# MioMicro.net
KiCad netlist of a schematic drawn in Altium Designer
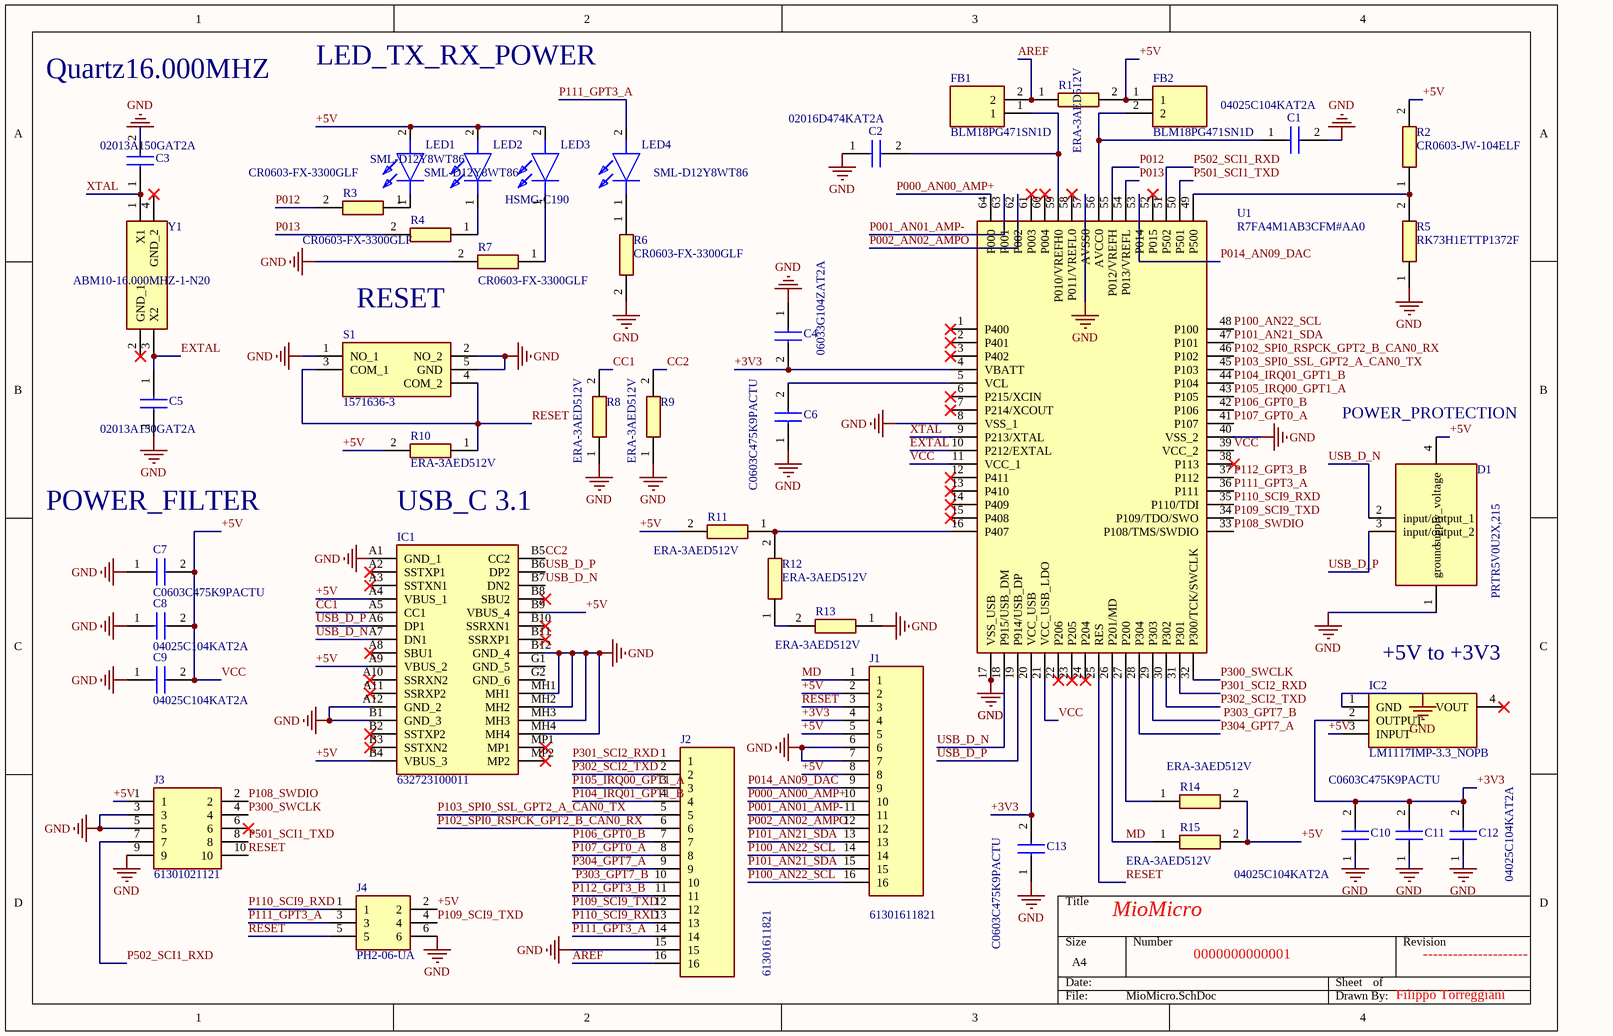
[diagram p0: MioMicro.SchDoc]

(export (version "E")
  (design (tool "Eeschema 10.0.6"))
  (components
    (comp (ref "C1")
      (value "04025C104KAT2A")
      (footprint "MioMicro:CAPC1005X56N")
      (description "Capacitor")
      (fields (field (name "MOUSER PART NUMBER") "581-04025C104KAT2A"))
      (libsource (lib "*") (part "04025C104KAT2A"))
    )
    (comp (ref "C2")
      (value "02016D474KAT2A")
      (footprint "MioMicro:CAPC0603X33N")
      (description "Capacitor")
      (fields (field (name "MOUSER PART NUMBER") "581-02016D474KAT2A"))
      (libsource (lib "*") (part "02016D474KAT2A"))
    )
    (comp (ref "C3")
      (value "02013A150GAT2A")
      (footprint "MioMicro:CAPC0603X33N")
      (description "Capacitor")
      (fields (field (name "MOUSER PART NUMBER") "581-02013A150GAT2A"))
      (libsource (lib "*") (part "02013A150GAT2A"))
    )
    (comp (ref "C4")
      (value "06033G104ZAT2A")
      (footprint "MioMicro:CAPC1608X90N")
      (description "Capacitor")
      (fields (field (name "MOUSER PART NUMBER") "581-06033G104Z"))
      (libsource (lib "*") (part "06033G104ZAT2A"))
    )
    (comp (ref "C5")
      (value "02013A150GAT2A")
      (footprint "MioMicro:CAPC0603X33N")
      (description "Capacitor")
      (fields (field (name "MOUSER PART NUMBER") "581-02013A150GAT2A"))
      (libsource (lib "*") (part "02013A150GAT2A"))
    )
    (comp (ref "C6")
      (value "C0603C475K9PACTU")
      (footprint "MioMicro:C0603")
      (description "Capacitor")
      (fields (field (name "MOUSER PART NUMBER") "80-C0603C475K9P"))
      (libsource (lib "*") (part "C0603C475K9PACTU"))
    )
    (comp (ref "C7")
      (value "C0603C475K9PACTU")
      (footprint "MioMicro:C0603")
      (description "Capacitor")
      (fields (field (name "MOUSER PART NUMBER") "80-C0603C475K9P"))
      (libsource (lib "*") (part "C0603C475K9PACTU"))
    )
    (comp (ref "C8")
      (value "04025C104KAT2A")
      (footprint "MioMicro:CAPC1005X56N")
      (description "Capacitor")
      (fields (field (name "MOUSER PART NUMBER") "581-04025C104KAT2A"))
      (libsource (lib "*") (part "04025C104KAT2A"))
    )
    (comp (ref "C9")
      (value "04025C104KAT2A")
      (footprint "MioMicro:CAPC1005X56N")
      (description "Capacitor")
      (fields (field (name "MOUSER PART NUMBER") "581-04025C104KAT2A"))
      (libsource (lib "*") (part "04025C104KAT2A"))
    )
    (comp (ref "C10")
      (value "C0603C475K9PACTU")
      (footprint "MioMicro:C0603")
      (description "Capacitor")
      (fields (field (name "MOUSER PART NUMBER") "80-C0603C475K9P"))
      (libsource (lib "*") (part "C0603C475K9PACTU"))
    )
    (comp (ref "C11")
      (value "04025C104KAT2A")
      (footprint "MioMicro:CAPC1005X56N")
      (description "Capacitor")
      (fields (field (name "MOUSER PART NUMBER") "581-04025C104KAT2A"))
      (libsource (lib "*") (part "04025C104KAT2A"))
    )
    (comp (ref "C12")
      (value "04025C104KAT2A")
      (footprint "MioMicro:CAPC1005X56N")
      (description "Capacitor")
      (fields (field (name "MOUSER PART NUMBER") "581-04025C104KAT2A"))
      (libsource (lib "*") (part "04025C104KAT2A"))
    )
    (comp (ref "C13")
      (value "C0603C475K9PACTU")
      (footprint "MioMicro:C0603")
      (description "Capacitor")
      (fields (field (name "MOUSER PART NUMBER") "80-C0603C475K9P"))
      (libsource (lib "*") (part "C0603C475K9PACTU"))
    )
    (comp (ref "D1")
      (value "PRTR5V0U2X,215")
      (footprint "MioMicro:PRTR5V0U2X")
      (description "Diode")
      (fields (field (name "MOUSER PART NUMBER") "771-PRTR5V0U2X-T/R"))
      (libsource (lib "*") (part "PRTR5V0U2X,215"))
    )
    (comp (ref "FB1")
      (value "BLM18PG471SN1D")
      (footprint "MioMicro:BLM18SP221SN1B")
      (description "Ferrite Bead")
      (fields (field (name "MOUSER PART NUMBER") "81-BLM18PG471SN1D"))
      (libsource (lib "") (part "BLM18PG471SN1D_1"))
    )
    (comp (ref "FB2")
      (value "BLM18PG471SN1D")
      (footprint "MioMicro:BLM18SP221SN1B")
      (description "Ferrite Bead")
      (fields (field (name "MOUSER PART NUMBER") "81-BLM18PG471SN1D"))
      (libsource (lib "*") (part "BLM18PG471SN1D"))
    )
    (comp (ref "IC1")
      (value "632723100011")
      (footprint "MioMicro:632723100011")
      (description "Integrated Circuit")
      (fields (field (name "MOUSER PART NUMBER") "710-632723100011"))
      (libsource (lib "*") (part "632723100011"))
    )
    (comp (ref "IC2")
      (value "LM1117IMP-3.3_NOPB")
      (footprint "MioMicro:SOT230P700X180-4N")
      (description "Integrated Circuit")
      (fields
        (field (name "MANUFACTURER_PART_NUMBER") "LM1117IMP-3.3/NOPB")
        (field (name "MOUSER PART NUMBER") "926-LM1117IMP3.3NOPB")
      )
      (libsource (lib "*") (part "LM1117IMP-3.3_NOPB"))
    )
    (comp (ref "J1")
      (value "61301611821")
      (footprint "MioMicro:RHDR16W82P0X254_1X16_4114X250X865P")
      (description "Connector")
      (fields (field (name "MOUSER PART NUMBER") "710-61301611821"))
      (libsource (lib "*") (part "61301611821"))
    )
    (comp (ref "J2")
      (value "61301611821")
      (footprint "MioMicro:RHDR16W82P0X254_1X16_4114X250X865P")
      (description "Connector")
      (fields (field (name "MOUSER PART NUMBER") "710-61301611821"))
      (libsource (lib "*") (part "61301611821"))
    )
    (comp (ref "J3")
      (value "61301021121")
      (footprint "MioMicro:HDRV10W64P254X254_2X5_1270X508X869P")
      (description "Connector")
      (fields (field (name "MOUSER PART NUMBER") "710-61301021121"))
      (libsource (lib "*") (part "61301021121"))
    )
    (comp (ref "J4")
      (value "PH2-06-UA")
      (footprint "MioMicro:HDRV6W64P254_2X3_762X500X901P")
      (description "Connector")
      (libsource (lib "*") (part "PH2-06-UA"))
    )
    (comp (ref "LED1")
      (value "SML-D12Y8WT86")
      (footprint "MioMicro:LEDM1620X150N")
      (description "LED")
      (fields (field (name "MOUSER PART NUMBER") "755-SML-D12Y8WT86"))
      (libsource (lib "*") (part "SML-D12Y8WT86"))
    )
    (comp (ref "LED2")
      (value "SML-D12Y8WT86")
      (footprint "MioMicro:LEDM1620X150N")
      (description "LED")
      (fields (field (name "MOUSER PART NUMBER") "755-SML-D12Y8WT86"))
      (libsource (lib "*") (part "SML-D12Y8WT86"))
    )
    (comp (ref "LED3")
      (value "HSMG-C190")
      (footprint "MioMicro:LEDC1608X90N")
      (description "LED")
      (fields (field (name "MOUSER PART NUMBER") "630-HSMG-C190"))
      (libsource (lib "*") (part "HSMG-C190"))
    )
    (comp (ref "LED4")
      (value "SML-D12Y8WT86")
      (footprint "MioMicro:LEDM1620X150N")
      (description "LED")
      (fields (field (name "MOUSER PART NUMBER") "755-SML-D12Y8WT86"))
      (libsource (lib "*") (part "SML-D12Y8WT86"))
    )
    (comp (ref "R1")
      (value "ERA-3AED512V")
      (footprint "MioMicro:ERA3AEB101V")
      (description "Resistor")
      (fields (field (name "MOUSER PART NUMBER") "667-ERA-3AED512V"))
      (libsource (lib "*") (part "ERA-3AED512V"))
    )
    (comp (ref "R2")
      (value "CR0603-JW-104ELF")
      (footprint "MioMicro:RESC1608X55N")
      (description "Resistor")
      (fields (field (name "MOUSER PART NUMBER") "652-CR0603-JW-104ELF"))
      (libsource (lib "*") (part "CR0603-JW-104ELF"))
    )
    (comp (ref "R3")
      (value "CR0603-FX-3300GLF")
      (footprint "MioMicro:RESC1608X55N")
      (description "Resistor")
      (fields (field (name "MOUSER PART NUMBER") "652-CR0603-FX3300GLF"))
      (libsource (lib "*") (part "CR0603-FX-3300GLF"))
    )
    (comp (ref "R4")
      (value "CR0603-FX-3300GLF")
      (footprint "MioMicro:RESC1608X55N")
      (description "Resistor")
      (fields (field (name "MOUSER PART NUMBER") "652-CR0603-FX3300GLF"))
      (libsource (lib "*") (part "CR0603-FX-3300GLF"))
    )
    (comp (ref "R5")
      (value "RK73H1ETTP1372F")
      (footprint "MioMicro:RESC1005X40N")
      (description "Resistor")
      (fields (field (name "MOUSER PART NUMBER") "660-RK73H1ETTP1372F"))
      (libsource (lib "*") (part "RK73H1ETTP1372F"))
    )
    (comp (ref "R6")
      (value "CR0603-FX-3300GLF")
      (footprint "MioMicro:RESC1608X55N")
      (description "Resistor")
      (fields (field (name "MOUSER PART NUMBER") "652-CR0603-FX3300GLF"))
      (libsource (lib "") (part "CR0603-FX-3300GLF_1"))
    )
    (comp (ref "R7")
      (value "CR0603-FX-3300GLF")
      (footprint "MioMicro:RESC1608X55N")
      (description "Resistor")
      (fields (field (name "MOUSER PART NUMBER") "652-CR0603-FX3300GLF"))
      (libsource (lib "*") (part "CR0603-FX-3300GLF"))
    )
    (comp (ref "R8")
      (value "ERA-3AED512V")
      (footprint "MioMicro:ERA3AEB101V")
      (description "Resistor")
      (fields (field (name "MOUSER PART NUMBER") "667-ERA-3AED512V"))
      (libsource (lib "") (part "ERA-3AED512V_1"))
    )
    (comp (ref "R9")
      (value "ERA-3AED512V")
      (footprint "MioMicro:ERA3AEB101V")
      (description "Resistor")
      (fields (field (name "MOUSER PART NUMBER") "667-ERA-3AED512V"))
      (libsource (lib "") (part "ERA-3AED512V_1"))
    )
    (comp (ref "R10")
      (value "ERA-3AED512V")
      (footprint "MioMicro:ERA3AEB101V")
      (description "Resistor")
      (fields (field (name "MOUSER PART NUMBER") "667-ERA-3AED512V"))
      (libsource (lib "") (part "ERA-3AED512V_2"))
    )
    (comp (ref "R11")
      (value "ERA-3AED512V")
      (footprint "MioMicro:ERA3AEB101V")
      (description "Resistor")
      (fields (field (name "MOUSER PART NUMBER") "667-ERA-3AED512V"))
      (libsource (lib "") (part "ERA-3AED512V_2"))
    )
    (comp (ref "R12")
      (value "ERA-3AED512V")
      (footprint "MioMicro:ERA3AEB101V")
      (description "Resistor")
      (fields (field (name "MOUSER PART NUMBER") "667-ERA-3AED512V"))
      (libsource (lib "") (part "ERA-3AED512V_1"))
    )
    (comp (ref "R13")
      (value "ERA-3AED512V")
      (footprint "MioMicro:ERA3AEB101V")
      (description "Resistor")
      (fields (field (name "MOUSER PART NUMBER") "667-ERA-3AED512V"))
      (libsource (lib "") (part "ERA-3AED512V_2"))
    )
    (comp (ref "R14")
      (value "ERA-3AED512V")
      (footprint "MioMicro:ERA3AEB101V")
      (description "Resistor")
      (fields (field (name "MOUSER PART NUMBER") "667-ERA-3AED512V"))
      (libsource (lib "*") (part "ERA-3AED512V"))
    )
    (comp (ref "R15")
      (value "ERA-3AED512V")
      (footprint "MioMicro:ERA3AEB101V")
      (description "Resistor")
      (fields (field (name "MOUSER PART NUMBER") "667-ERA-3AED512V"))
      (libsource (lib "*") (part "ERA-3AED512V"))
    )
    (comp (ref "S1")
      (value "1571636-3")
      (footprint "MioMicro:15716363")
      (description "Switch")
      (fields (field (name "MOUSER PART NUMBER") "506-1571636-3"))
      (libsource (lib "*") (part "1571636-3"))
    )
    (comp (ref "U1")
      (value "R7FA4M1AB3CFM#AA0")
      (footprint "MioMicro:QFP50P1200X1200X170-64N")
      (description "Integrated Circuit")
      (fields (field (name "MOUSER PART NUMBER") "968-7FA4M1AB3CFM#AA0"))
      (libsource (lib "*") (part "R7FA4M1AB3CFM#AA0"))
    )
    (comp (ref "Y1")
      (value "ABM10-16.000MHZ-1-N20")
      (footprint "MioMicro:ABM10")
      (description "Crystal or Oscillator")
      (libsource (lib "*") (part "ABM10-16.000MHZ-1-N20"))
    )
  )
  (nets
    (net (code "1") (name "/ P303_GPT7_B") (class "Default")
      (node (ref "J2") (pin "10") (pinfunction "10_10") (pintype "passive"))
      (node (ref "U1") (pin "29") (pinfunction "P303_29") (pintype "passive"))
    )
    (net (code "2") (name "/+3V3") (class "Default")
      (node (ref "C10") (pin "2") (pinfunction "2_2") (pintype "passive"))
      (node (ref "C11") (pin "2") (pinfunction "2_2") (pintype "passive"))
      (node (ref "C12") (pin "2") (pinfunction "2_2") (pintype "passive"))
      (node (ref "C13") (pin "2") (pinfunction "2_2") (pintype "passive"))
      (node (ref "C4") (pin "2") (pinfunction "2_2") (pintype "passive"))
      (node (ref "IC2") (pin "2") (pinfunction "OUTPUT_2") (pintype "passive"))
      (node (ref "J1") (pin "4") (pinfunction "4_4") (pintype "passive"))
      (node (ref "U1") (pin "20") (pinfunction "VCC_USB_20") (pintype "passive"))
      (node (ref "U1") (pin "4") (pinfunction "VBATT_4") (pintype "passive"))
    )
    (net (code "3") (name "/+5V") (class "Default")
      (node (ref "C7") (pin "2") (pinfunction "2_2") (pintype "passive"))
      (node (ref "C8") (pin "2") (pinfunction "2_2") (pintype "passive"))
      (node (ref "C9") (pin "2") (pinfunction "2_2") (pintype "passive"))
      (node (ref "D1") (pin "4") (pinfunction "supply_voltage_4") (pintype "passive"))
      (node (ref "FB2") (pin "1") (pinfunction "1_1") (pintype "passive"))
      (node (ref "IC1") (pin "A4") (pinfunction "VBUS_1_A4") (pintype "passive"))
      (node (ref "IC1") (pin "A9") (pinfunction "VBUS_2_A9") (pintype "passive"))
      (node (ref "IC1") (pin "B4") (pinfunction "VBUS_3_B4") (pintype "passive"))
      (node (ref "IC1") (pin "B9") (pinfunction "VBUS_4_B9") (pintype "passive"))
      (node (ref "IC2") (pin "3") (pinfunction "INPUT_3") (pintype "passive"))
      (node (ref "J1") (pin "2") (pinfunction "2_2") (pintype "passive"))
      (node (ref "J1") (pin "5") (pinfunction "5_5") (pintype "passive"))
      (node (ref "J1") (pin "8") (pinfunction "8_8") (pintype "passive"))
      (node (ref "J3") (pin "1") (pinfunction "1_1") (pintype "passive"))
      (node (ref "J4") (pin "2") (pinfunction "2_2") (pintype "passive"))
      (node (ref "LED1") (pin "2") (pinfunction "A_2") (pintype "passive"))
      (node (ref "LED2") (pin "2") (pinfunction "A_2") (pintype "passive"))
      (node (ref "LED3") (pin "2") (pinfunction "A_2") (pintype "passive"))
      (node (ref "R1") (pin "2") (pinfunction "2_2") (pintype "passive"))
      (node (ref "R10") (pin "2") (pinfunction "2_2") (pintype "passive"))
      (node (ref "R11") (pin "2") (pinfunction "2_2") (pintype "passive"))
      (node (ref "R14") (pin "2") (pinfunction "2_2") (pintype "passive"))
      (node (ref "R15") (pin "2") (pinfunction "2_2") (pintype "passive"))
      (node (ref "R2") (pin "2") (pinfunction "2_2") (pintype "passive"))
      (node (ref "U1") (pin "11") (pinfunction "VCC_1_11") (pintype "passive"))
      (node (ref "U1") (pin "21") (pinfunction "VCC_USB_LDO_21") (pintype "passive"))
      (node (ref "U1") (pin "39") (pinfunction "VCC_2_39") (pintype "passive"))
    )
    (net (code "4") (name "/AREF") (class "Default")
      (node (ref "FB1") (pin "2") (pinfunction "2_2") (pintype "passive"))
      (node (ref "J2") (pin "16") (pinfunction "16_16") (pintype "passive"))
      (node (ref "R1") (pin "1") (pinfunction "1_1") (pintype "passive"))
    )
    (net (code "5") (name "/CC1") (class "Default")
      (node (ref "IC1") (pin "A5") (pinfunction "CC1_A5") (pintype "passive"))
      (node (ref "R8") (pin "2") (pinfunction "2_2") (pintype "passive"))
    )
    (net (code "6") (name "/CC2") (class "Default")
      (node (ref "IC1") (pin "B5") (pinfunction "CC2_B5") (pintype "passive"))
      (node (ref "R9") (pin "2") (pinfunction "2_2") (pintype "passive"))
    )
    (net (code "7") (name "/EXTAL") (class "Default")
      (node (ref "C5") (pin "1") (pinfunction "1_1") (pintype "passive"))
      (node (ref "U1") (pin "10") (pinfunction "P212/EXTAL_10") (pintype "passive"))
      (node (ref "Y1") (pin "3") (pinfunction "X2_3") (pintype "passive"))
    )
    (net (code "8") (name "/MD") (class "Default")
      (node (ref "J1") (pin "1") (pinfunction "1_1") (pintype "passive"))
      (node (ref "R15") (pin "1") (pinfunction "1_1") (pintype "passive"))
      (node (ref "U1") (pin "26") (pinfunction "P201/MD_26") (pintype "passive"))
    )
    (net (code "9") (name "/P000_AN00_AMP+") (class "Default")
      (node (ref "J1") (pin "10") (pinfunction "10_10") (pintype "passive"))
      (node (ref "U1") (pin "64") (pinfunction "P000_64") (pintype "passive"))
    )
    (net (code "10") (name "/P001_AN01_AMP-") (class "Default")
      (node (ref "J1") (pin "11") (pinfunction "11_11") (pintype "passive"))
      (node (ref "U1") (pin "63") (pinfunction "P001_63") (pintype "passive"))
    )
    (net (code "11") (name "/P002_AN02_AMPO") (class "Default")
      (node (ref "J1") (pin "12") (pinfunction "12_12") (pintype "passive"))
      (node (ref "U1") (pin "62") (pinfunction "P002_62") (pintype "passive"))
    )
    (net (code "12") (name "/P012") (class "Default")
      (node (ref "R3") (pin "2") (pinfunction "2_2") (pintype "passive"))
      (node (ref "U1") (pin "55") (pinfunction "P012/VREFH_55") (pintype "passive"))
    )
    (net (code "13") (name "/P013") (class "Default")
      (node (ref "R4") (pin "2") (pinfunction "2_2") (pintype "passive"))
      (node (ref "U1") (pin "54") (pinfunction "P013/VREFL_54") (pintype "passive"))
    )
    (net (code "14") (name "/P014_AN09_DAC") (class "Default")
      (node (ref "J1") (pin "9") (pinfunction "9_9") (pintype "passive"))
      (node (ref "U1") (pin "53") (pinfunction "P014_53") (pintype "passive"))
    )
    (net (code "15") (name "/P100_AN22_SCL") (class "Default")
      (node (ref "J1") (pin "14") (pinfunction "14_14") (pintype "passive"))
      (node (ref "J1") (pin "16") (pinfunction "16_16") (pintype "passive"))
      (node (ref "U1") (pin "48") (pinfunction "P100_48") (pintype "passive"))
    )
    (net (code "16") (name "/P101_AN21_SDA") (class "Default")
      (node (ref "J1") (pin "13") (pinfunction "13_13") (pintype "passive"))
      (node (ref "J1") (pin "15") (pinfunction "15_15") (pintype "passive"))
      (node (ref "U1") (pin "47") (pinfunction "P101_47") (pintype "passive"))
    )
    (net (code "17") (name "/P102_SPI0_RSPCK_GPT2_B_CAN0_RX") (class "Default")
      (node (ref "J2") (pin "6") (pinfunction "6_6") (pintype "passive"))
      (node (ref "U1") (pin "46") (pinfunction "P102_46") (pintype "passive"))
    )
    (net (code "18") (name "/P103_SPI0_SSL_GPT2_A_CAN0_TX") (class "Default")
      (node (ref "J2") (pin "5") (pinfunction "5_5") (pintype "passive"))
      (node (ref "U1") (pin "45") (pinfunction "P103_45") (pintype "passive"))
    )
    (net (code "19") (name "/P104_IRQ01_GPT1_B") (class "Default")
      (node (ref "J2") (pin "4") (pinfunction "4_4") (pintype "passive"))
      (node (ref "U1") (pin "44") (pinfunction "P104_44") (pintype "passive"))
    )
    (net (code "20") (name "/P105_IRQ00_GPT1_A") (class "Default")
      (node (ref "J2") (pin "3") (pinfunction "3_3") (pintype "passive"))
      (node (ref "U1") (pin "43") (pinfunction "P105_43") (pintype "passive"))
    )
    (net (code "21") (name "/P106_GPT0_B") (class "Default")
      (node (ref "J2") (pin "7") (pinfunction "7_7") (pintype "passive"))
      (node (ref "U1") (pin "42") (pinfunction "P106_42") (pintype "passive"))
    )
    (net (code "22") (name "/P107_GPT0_A") (class "Default")
      (node (ref "J2") (pin "8") (pinfunction "8_8") (pintype "passive"))
      (node (ref "U1") (pin "41") (pinfunction "P107_41") (pintype "passive"))
    )
    (net (code "23") (name "/P108_SWDIO") (class "Default")
      (node (ref "J3") (pin "2") (pinfunction "2_2") (pintype "passive"))
      (node (ref "U1") (pin "33") (pinfunction "P108/TMS/SWDIO_33") (pintype "passive"))
    )
    (net (code "24") (name "/P109_SCI9_TXD") (class "Default")
      (node (ref "J2") (pin "12") (pinfunction "12_12") (pintype "passive"))
      (node (ref "J4") (pin "4") (pinfunction "4_4") (pintype "passive"))
      (node (ref "U1") (pin "34") (pinfunction "P109/TDO/SWO_34") (pintype "passive"))
    )
    (net (code "25") (name "/P110_SCI9_RXD") (class "Default")
      (node (ref "J2") (pin "13") (pinfunction "13_13") (pintype "passive"))
      (node (ref "J4") (pin "1") (pinfunction "1_1") (pintype "passive"))
      (node (ref "U1") (pin "35") (pinfunction "P110/TDI_35") (pintype "passive"))
    )
    (net (code "26") (name "/P111_GPT3_A") (class "Default")
      (node (ref "J2") (pin "14") (pinfunction "14_14") (pintype "passive"))
      (node (ref "J4") (pin "3") (pinfunction "3_3") (pintype "passive"))
      (node (ref "LED4") (pin "2") (pinfunction "A_2") (pintype "passive"))
      (node (ref "U1") (pin "36") (pinfunction "P111_36") (pintype "passive"))
    )
    (net (code "27") (name "/P112_GPT3_B") (class "Default")
      (node (ref "J2") (pin "11") (pinfunction "11_11") (pintype "passive"))
      (node (ref "U1") (pin "37") (pinfunction "P112_37") (pintype "passive"))
    )
    (net (code "28") (name "/P300_SWCLK") (class "Default")
      (node (ref "J3") (pin "4") (pinfunction "4_4") (pintype "passive"))
      (node (ref "U1") (pin "32") (pinfunction "P300/TCK/SWCLK_32") (pintype "passive"))
    )
    (net (code "29") (name "/P301_SCI2_RXD") (class "Default")
      (node (ref "J2") (pin "1") (pinfunction "1_1") (pintype "passive"))
      (node (ref "U1") (pin "31") (pinfunction "P301_31") (pintype "passive"))
    )
    (net (code "30") (name "/P302_SCI2_TXD") (class "Default")
      (node (ref "J2") (pin "2") (pinfunction "2_2") (pintype "passive"))
      (node (ref "U1") (pin "30") (pinfunction "P302_30") (pintype "passive"))
    )
    (net (code "31") (name "/P304_GPT7_A") (class "Default")
      (node (ref "J2") (pin "9") (pinfunction "9_9") (pintype "passive"))
      (node (ref "U1") (pin "28") (pinfunction "P304_28") (pintype "passive"))
    )
    (net (code "32") (name "/P501_SCI1_TXD") (class "Default")
      (node (ref "J3") (pin "8") (pinfunction "8_8") (pintype "passive"))
      (node (ref "U1") (pin "50") (pinfunction "P501_50") (pintype "passive"))
    )
    (net (code "33") (name "/P502_SCI1_RXD") (class "Default")
      (node (ref "J3") (pin "7") (pinfunction "7_7") (pintype "passive"))
      (node (ref "U1") (pin "51") (pinfunction "P502_51") (pintype "passive"))
    )
    (net (code "34") (name "/RESET") (class "Default")
      (node (ref "J1") (pin "3") (pinfunction "3_3") (pintype "passive"))
      (node (ref "J3") (pin "10") (pinfunction "10_10") (pintype "passive"))
      (node (ref "J4") (pin "5") (pinfunction "5_5") (pintype "passive"))
      (node (ref "R10") (pin "1") (pinfunction "1_1") (pintype "passive"))
      (node (ref "S1") (pin "3") (pinfunction "COM_1_3") (pintype "passive"))
      (node (ref "S1") (pin "4") (pinfunction "COM_2_4") (pintype "passive"))
      (node (ref "U1") (pin "25") (pinfunction "RES_25") (pintype "passive"))
    )
    (net (code "35") (name "/USB_D_N") (class "Default")
      (node (ref "D1") (pin "2") (pinfunction "input/output_1_2") (pintype "passive"))
      (node (ref "IC1") (pin "A7") (pinfunction "DN1_A7") (pintype "passive"))
      (node (ref "IC1") (pin "B7") (pinfunction "DN2_B7") (pintype "passive"))
      (node (ref "U1") (pin "18") (pinfunction "P915/USB_DM_18") (pintype "passive"))
    )
    (net (code "36") (name "/USB_D_P") (class "Default")
      (node (ref "D1") (pin "3") (pinfunction "input/output_2_3") (pintype "passive"))
      (node (ref "IC1") (pin "A6") (pinfunction "DP1_A6") (pintype "passive"))
      (node (ref "IC1") (pin "B6") (pinfunction "DP2_B6") (pintype "passive"))
      (node (ref "U1") (pin "19") (pinfunction "P914/USB_DP_19") (pintype "passive"))
    )
    (net (code "37") (name "/XTAL") (class "Default")
      (node (ref "C3") (pin "1") (pinfunction "1_1") (pintype "passive"))
      (node (ref "U1") (pin "9") (pinfunction "P213/XTAL_9") (pintype "passive"))
      (node (ref "Y1") (pin "1") (pinfunction "X1_1") (pintype "passive"))
    )
    (net (code "38") (name "GND") (class "Default")
      (node (ref "C1") (pin "2") (pinfunction "2_2") (pintype "passive"))
      (node (ref "C10") (pin "1") (pinfunction "1_1") (pintype "passive"))
      (node (ref "C11") (pin "1") (pinfunction "1_1") (pintype "passive"))
      (node (ref "C12") (pin "1") (pinfunction "1_1") (pintype "passive"))
      (node (ref "C13") (pin "1") (pinfunction "1_1") (pintype "passive"))
      (node (ref "C2") (pin "1") (pinfunction "1_1") (pintype "passive"))
      (node (ref "C3") (pin "2") (pinfunction "2_2") (pintype "passive"))
      (node (ref "C4") (pin "1") (pinfunction "1_1") (pintype "passive"))
      (node (ref "C5") (pin "2") (pinfunction "2_2") (pintype "passive"))
      (node (ref "C6") (pin "1") (pinfunction "1_1") (pintype "passive"))
      (node (ref "C7") (pin "1") (pinfunction "1_1") (pintype "passive"))
      (node (ref "C8") (pin "1") (pinfunction "1_1") (pintype "passive"))
      (node (ref "C9") (pin "1") (pinfunction "1_1") (pintype "passive"))
      (node (ref "D1") (pin "1") (pinfunction "ground_1") (pintype "passive"))
      (node (ref "IC1") (pin "A1") (pinfunction "GND_1_A1") (pintype "passive"))
      (node (ref "IC1") (pin "A12") (pinfunction "GND_2_A12") (pintype "passive"))
      (node (ref "IC1") (pin "B1") (pinfunction "GND_3_B1") (pintype "passive"))
      (node (ref "IC1") (pin "B12") (pinfunction "GND_4_B12") (pintype "passive"))
      (node (ref "IC1") (pin "MH1") (pinfunction "MH1_MH1") (pintype "passive"))
      (node (ref "IC1") (pin "MH2") (pinfunction "MH2_MH2") (pintype "passive"))
      (node (ref "IC1") (pin "MH3") (pinfunction "MH3_MH3") (pintype "passive"))
      (node (ref "IC1") (pin "MH4") (pinfunction "MH4_MH4") (pintype "passive"))
      (node (ref "IC2") (pin "1") (pinfunction "GND_1") (pintype "passive"))
      (node (ref "J1") (pin "6") (pinfunction "6_6") (pintype "passive"))
      (node (ref "J1") (pin "7") (pinfunction "7_7") (pintype "passive"))
      (node (ref "J2") (pin "15") (pinfunction "15_15") (pintype "passive"))
      (node (ref "J3") (pin "3") (pinfunction "3_3") (pintype "passive"))
      (node (ref "J3") (pin "5") (pinfunction "5_5") (pintype "passive"))
      (node (ref "J3") (pin "9") (pinfunction "9_9") (pintype "passive"))
      (node (ref "J4") (pin "6") (pinfunction "6_6") (pintype "passive"))
      (node (ref "R13") (pin "1") (pinfunction "1_1") (pintype "passive"))
      (node (ref "R5") (pin "1") (pinfunction "1_1") (pintype "passive"))
      (node (ref "R6") (pin "2") (pinfunction "2_2") (pintype "passive"))
      (node (ref "R7") (pin "2") (pinfunction "2_2") (pintype "passive"))
      (node (ref "R8") (pin "1") (pinfunction "1_1") (pintype "passive"))
      (node (ref "R9") (pin "1") (pinfunction "1_1") (pintype "passive"))
      (node (ref "S1") (pin "1") (pinfunction "NO_1_1") (pintype "passive"))
      (node (ref "S1") (pin "2") (pinfunction "NO_2_2") (pintype "passive"))
      (node (ref "S1") (pin "5") (pinfunction "GND_5") (pintype "passive"))
      (node (ref "U1") (pin "17") (pinfunction "VSS_USB_17") (pintype "passive"))
      (node (ref "U1") (pin "40") (pinfunction "VSS_2_40") (pintype "passive"))
      (node (ref "U1") (pin "57") (pinfunction "AVSS0_57") (pintype "passive"))
      (node (ref "U1") (pin "8") (pinfunction "VSS_1_8") (pintype "passive"))
    )
    (net (code "39") (name "Net-(LED1-K)") (class "Default")
      (node (ref "LED1") (pin "1") (pinfunction "K_1") (pintype "passive"))
      (node (ref "R3") (pin "1") (pinfunction "1_1") (pintype "passive"))
    )
    (net (code "40") (name "Net-(LED2-K)") (class "Default")
      (node (ref "LED2") (pin "1") (pinfunction "K_1") (pintype "passive"))
      (node (ref "R4") (pin "1") (pinfunction "1_1") (pintype "passive"))
    )
    (net (code "41") (name "Net-(LED3-K)") (class "Default")
      (node (ref "LED3") (pin "1") (pinfunction "K_1") (pintype "passive"))
      (node (ref "R7") (pin "1") (pinfunction "1_1") (pintype "passive"))
    )
    (net (code "42") (name "Net-(LED4-K)") (class "Default")
      (node (ref "LED4") (pin "1") (pinfunction "K_1") (pintype "passive"))
      (node (ref "R6") (pin "1") (pinfunction "1_1") (pintype "passive"))
    )
    (net (code "43") (name "Net-(R12-Pad1)") (class "Default")
      (node (ref "R12") (pin "1") (pinfunction "1_1") (pintype "passive"))
      (node (ref "R13") (pin "2") (pinfunction "2_2") (pintype "passive"))
    )
    (net (code "44") (name "Net-(U1-AVCC0)") (class "Default")
      (node (ref "C1") (pin "1") (pinfunction "1_1") (pintype "passive"))
      (node (ref "FB2") (pin "2") (pinfunction "2_2") (pintype "passive"))
      (node (ref "U1") (pin "56") (pinfunction "AVCC0_56") (pintype "passive"))
    )
    (net (code "45") (name "Net-(U1-P010{slash}VREFH0)") (class "Default")
      (node (ref "C2") (pin "2") (pinfunction "2_2") (pintype "passive"))
      (node (ref "FB1") (pin "1") (pinfunction "1_1") (pintype "passive"))
      (node (ref "U1") (pin "59") (pinfunction "P010/VREFH0_59") (pintype "passive"))
    )
    (net (code "46") (name "Net-(U1-P200)") (class "Default")
      (node (ref "R14") (pin "1") (pinfunction "1_1") (pintype "passive"))
      (node (ref "U1") (pin "27") (pinfunction "P200_27") (pintype "passive"))
    )
    (net (code "47") (name "Net-(U1-P407)") (class "Default")
      (node (ref "R11") (pin "1") (pinfunction "1_1") (pintype "passive"))
      (node (ref "R12") (pin "2") (pinfunction "2_2") (pintype "passive"))
      (node (ref "U1") (pin "16") (pinfunction "P407_16") (pintype "passive"))
    )
    (net (code "48") (name "Net-(U1-P500)") (class "Default")
      (node (ref "R2") (pin "1") (pinfunction "1_1") (pintype "passive"))
      (node (ref "R5") (pin "2") (pinfunction "2_2") (pintype "passive"))
      (node (ref "U1") (pin "49") (pinfunction "P500_49") (pintype "passive"))
    )
    (net (code "49") (name "Net-(U1-VCL)") (class "Default")
      (node (ref "C6") (pin "2") (pinfunction "2_2") (pintype "passive"))
      (node (ref "U1") (pin "5") (pinfunction "VCL_5") (pintype "passive"))
    )
    (net (code "50") (name "unconnected-(IC1-GND_5-PadG1)") (class "Default")
      (node (ref "IC1") (pin "G1") (pinfunction "GND_5_G1") (pintype "passive"))
    )
    (net (code "51") (name "unconnected-(IC1-GND_6-PadG2)") (class "Default")
      (node (ref "IC1") (pin "G2") (pinfunction "GND_6_G2") (pintype "passive"))
    )
    (net (code "52") (name "unconnected-(IC1-PadMP1)") (class "Default")
      (node (ref "IC1") (pin "MP1") (pinfunction "MP1_MP1") (pintype "passive+no_connect"))
    )
    (net (code "53") (name "unconnected-(IC1-PadMP2)") (class "Default")
      (node (ref "IC1") (pin "MP2") (pinfunction "MP2_MP2") (pintype "passive+no_connect"))
    )
    (net (code "54") (name "unconnected-(IC1-SBU1-PadA8)") (class "Default")
      (node (ref "IC1") (pin "A8") (pinfunction "SBU1_A8") (pintype "passive+no_connect"))
    )
    (net (code "55") (name "unconnected-(IC1-SBU2-PadB8)") (class "Default")
      (node (ref "IC1") (pin "B8") (pinfunction "SBU2_B8") (pintype "passive+no_connect"))
    )
    (net (code "56") (name "unconnected-(IC1-SSRXN1-PadB10)") (class "Default")
      (node (ref "IC1") (pin "B10") (pinfunction "SSRXN1_B10") (pintype "passive+no_connect"))
    )
    (net (code "57") (name "unconnected-(IC1-SSRXN2-PadA10)") (class "Default")
      (node (ref "IC1") (pin "A10") (pinfunction "SSRXN2_A10") (pintype "passive+no_connect"))
    )
    (net (code "58") (name "unconnected-(IC1-SSRXP1-PadB11)") (class "Default")
      (node (ref "IC1") (pin "B11") (pinfunction "SSRXP1_B11") (pintype "passive+no_connect"))
    )
    (net (code "59") (name "unconnected-(IC1-SSRXP2-PadA11)") (class "Default")
      (node (ref "IC1") (pin "A11") (pinfunction "SSRXP2_A11") (pintype "passive+no_connect"))
    )
    (net (code "60") (name "unconnected-(IC1-SSTXN1-PadA3)") (class "Default")
      (node (ref "IC1") (pin "A3") (pinfunction "SSTXN1_A3") (pintype "passive+no_connect"))
    )
    (net (code "61") (name "unconnected-(IC1-SSTXN2-PadB3)") (class "Default")
      (node (ref "IC1") (pin "B3") (pinfunction "SSTXN2_B3") (pintype "passive+no_connect"))
    )
    (net (code "62") (name "unconnected-(IC1-SSTXP1-PadA2)") (class "Default")
      (node (ref "IC1") (pin "A2") (pinfunction "SSTXP1_A2") (pintype "passive+no_connect"))
    )
    (net (code "63") (name "unconnected-(IC1-SSTXP2-PadB2)") (class "Default")
      (node (ref "IC1") (pin "B2") (pinfunction "SSTXP2_B2") (pintype "passive+no_connect"))
    )
    (net (code "64") (name "unconnected-(IC2-VOUT-Pad4)") (class "Default")
      (node (ref "IC2") (pin "4") (pinfunction "VOUT_4") (pintype "passive+no_connect"))
    )
    (net (code "65") (name "unconnected-(J3-Pad6)") (class "Default")
      (node (ref "J3") (pin "6") (pinfunction "6_6") (pintype "passive+no_connect"))
    )
    (net (code "66") (name "unconnected-(U1-P003-Pad61)") (class "Default")
      (node (ref "U1") (pin "61") (pinfunction "P003_61") (pintype "passive+no_connect"))
    )
    (net (code "67") (name "unconnected-(U1-P004-Pad60)") (class "Default")
      (node (ref "U1") (pin "60") (pinfunction "P004_60") (pintype "passive+no_connect"))
    )
    (net (code "68") (name "unconnected-(U1-P011{slash}VREFL0-Pad58)") (class "Default")
      (node (ref "U1") (pin "58") (pinfunction "P011/VREFL0_58") (pintype "passive+no_connect"))
    )
    (net (code "69") (name "unconnected-(U1-P015-Pad52)") (class "Default")
      (node (ref "U1") (pin "52") (pinfunction "P015_52") (pintype "passive+no_connect"))
    )
    (net (code "70") (name "unconnected-(U1-P113-Pad38)") (class "Default")
      (node (ref "U1") (pin "38") (pinfunction "P113_38") (pintype "passive+no_connect"))
    )
    (net (code "71") (name "unconnected-(U1-P204-Pad24)") (class "Default")
      (node (ref "U1") (pin "24") (pinfunction "P204_24") (pintype "passive+no_connect"))
    )
    (net (code "72") (name "unconnected-(U1-P205-Pad23)") (class "Default")
      (node (ref "U1") (pin "23") (pinfunction "P205_23") (pintype "passive+no_connect"))
    )
    (net (code "73") (name "unconnected-(U1-P206-Pad22)") (class "Default")
      (node (ref "U1") (pin "22") (pinfunction "P206_22") (pintype "passive+no_connect"))
    )
    (net (code "74") (name "unconnected-(U1-P214{slash}XCOUT-Pad7)") (class "Default")
      (node (ref "U1") (pin "7") (pinfunction "P214/XCOUT_7") (pintype "passive+no_connect"))
    )
    (net (code "75") (name "unconnected-(U1-P215{slash}XCIN-Pad6)") (class "Default")
      (node (ref "U1") (pin "6") (pinfunction "P215/XCIN_6") (pintype "passive+no_connect"))
    )
    (net (code "76") (name "unconnected-(U1-P400-Pad1)") (class "Default")
      (node (ref "U1") (pin "1") (pinfunction "P400_1") (pintype "passive+no_connect"))
    )
    (net (code "77") (name "unconnected-(U1-P401-Pad2)") (class "Default")
      (node (ref "U1") (pin "2") (pinfunction "P401_2") (pintype "passive+no_connect"))
    )
    (net (code "78") (name "unconnected-(U1-P402-Pad3)") (class "Default")
      (node (ref "U1") (pin "3") (pinfunction "P402_3") (pintype "passive+no_connect"))
    )
    (net (code "79") (name "unconnected-(U1-P408-Pad15)") (class "Default")
      (node (ref "U1") (pin "15") (pinfunction "P408_15") (pintype "passive+no_connect"))
    )
    (net (code "80") (name "unconnected-(U1-P409-Pad14)") (class "Default")
      (node (ref "U1") (pin "14") (pinfunction "P409_14") (pintype "passive+no_connect"))
    )
    (net (code "81") (name "unconnected-(U1-P410-Pad13)") (class "Default")
      (node (ref "U1") (pin "13") (pinfunction "P410_13") (pintype "passive+no_connect"))
    )
    (net (code "82") (name "unconnected-(U1-P411-Pad12)") (class "Default")
      (node (ref "U1") (pin "12") (pinfunction "P411_12") (pintype "passive+no_connect"))
    )
    (net (code "83") (name "unconnected-(Y1-GND_1-Pad2)") (class "Default")
      (node (ref "Y1") (pin "2") (pinfunction "GND_1_2") (pintype "passive+no_connect"))
    )
    (net (code "84") (name "unconnected-(Y1-GND_2-Pad4)") (class "Default")
      (node (ref "Y1") (pin "4") (pinfunction "GND_2_4") (pintype "passive+no_connect"))
    )
  )
)
